# Main.net
KiCad netlist of a schematic drawn in Altium Designer
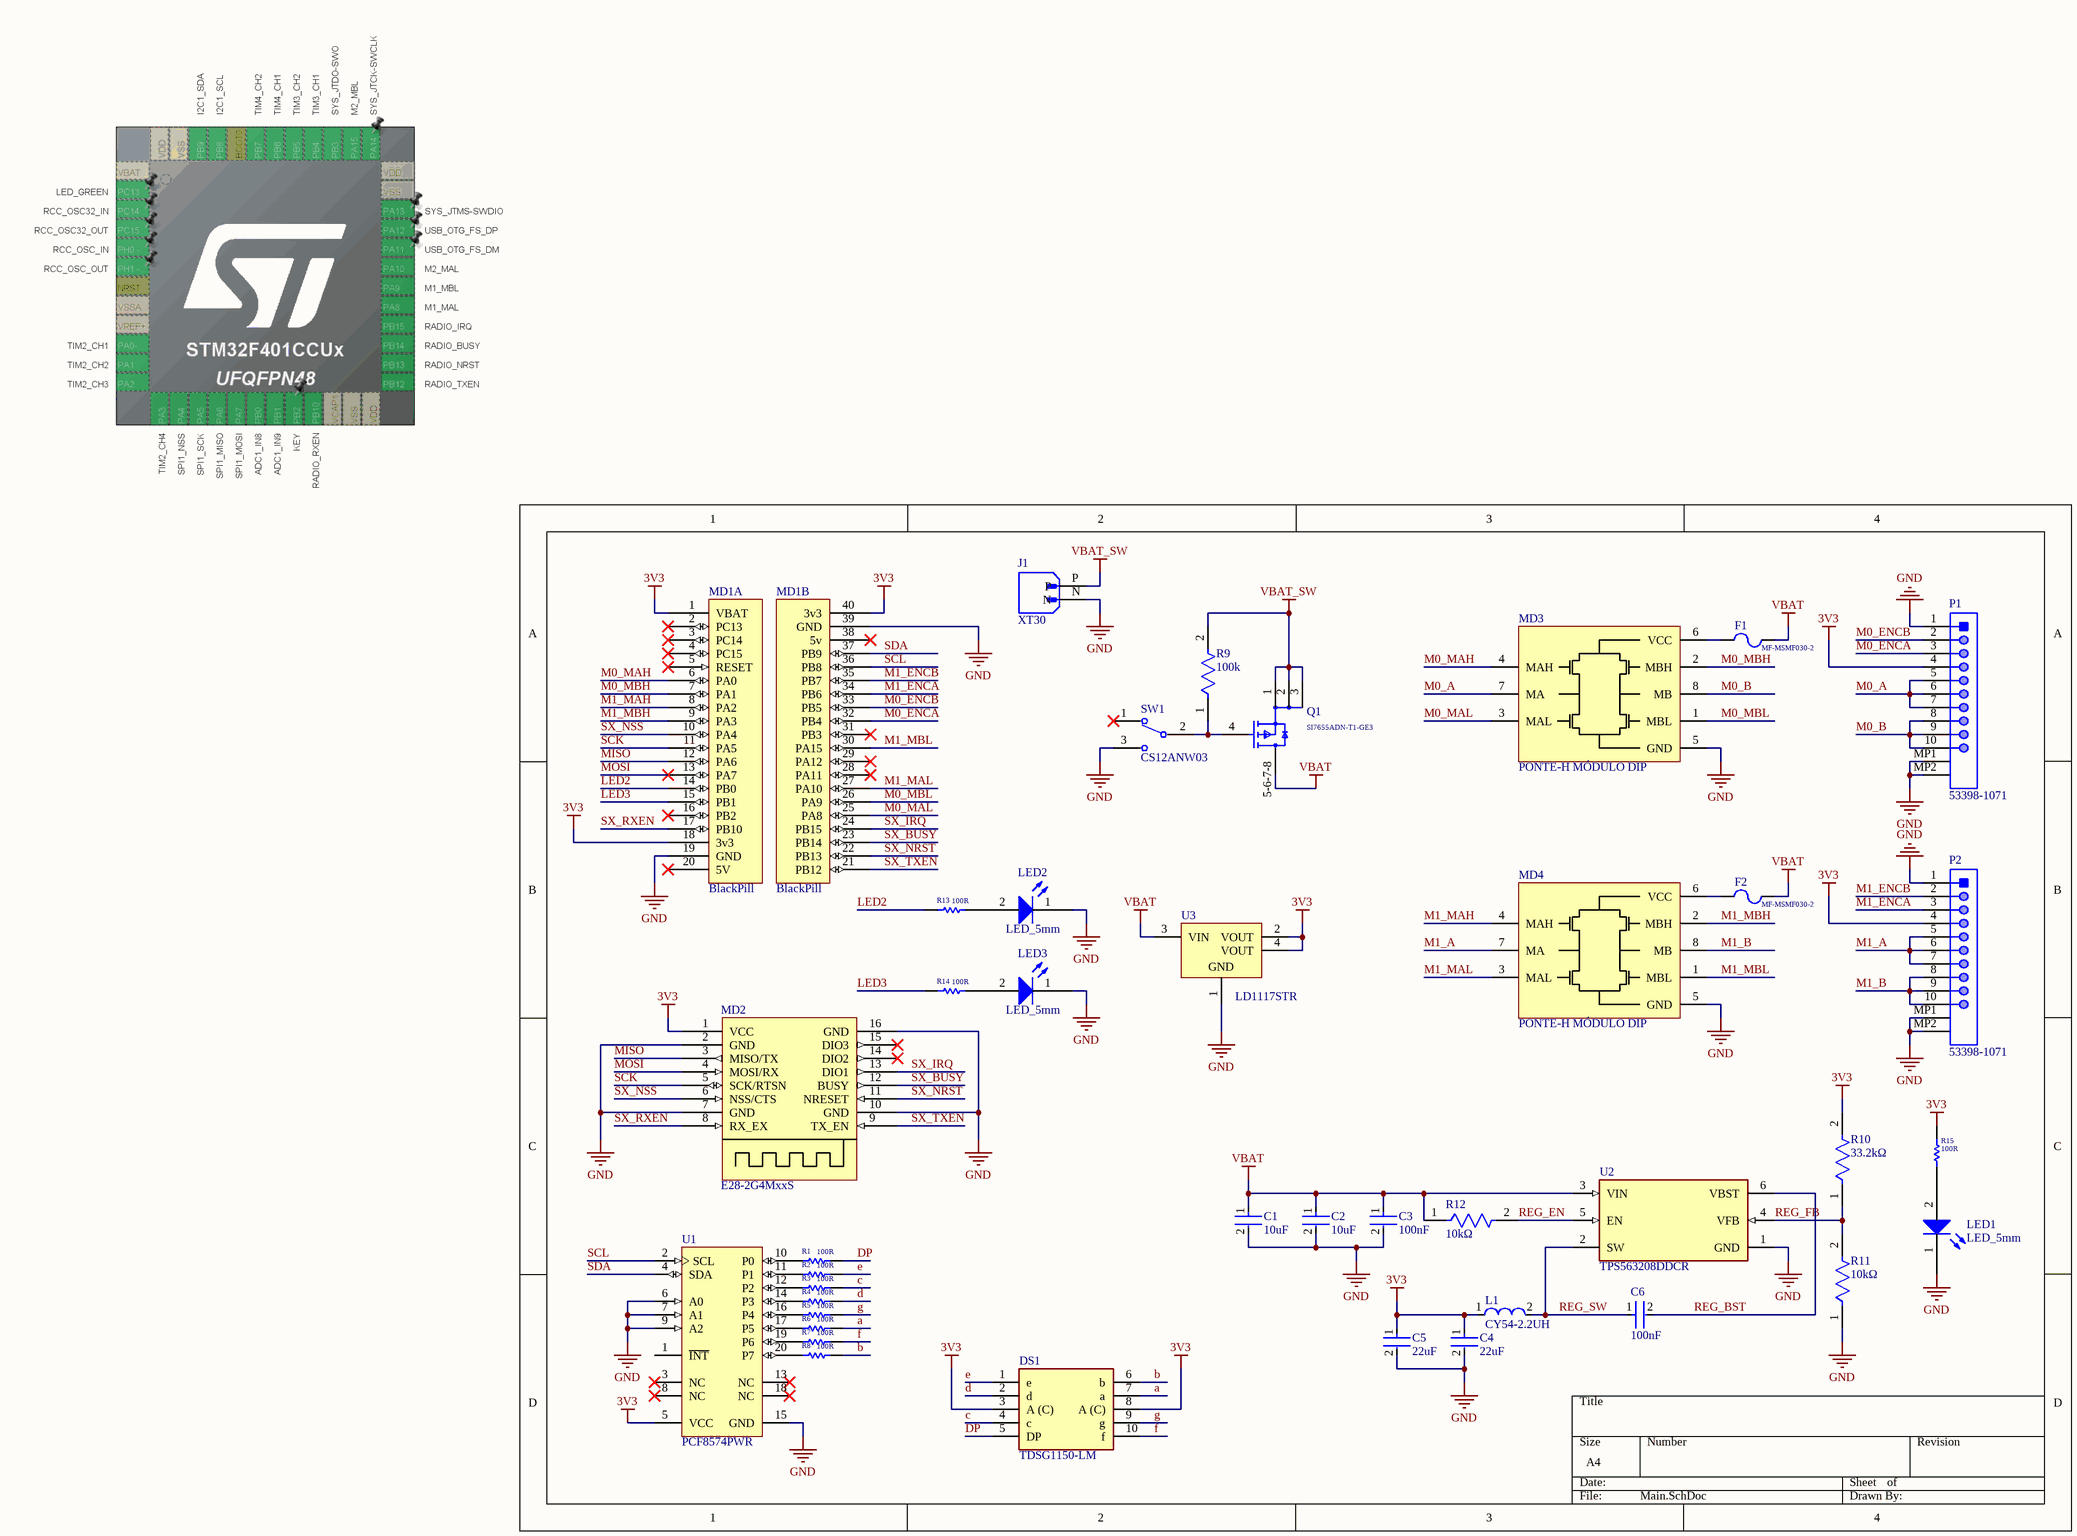
[diagram p0: Main.SchDoc]

(export (version "E")
  (design (tool "Eeschema 10.0.6"))
  (components
    (comp (ref "C1")
      (value "10uF")
      (footprint "FP-CL21-IPC_C")
      (description "CL21 Series 0805 10uF 16V ±10% Tolerance X5R Multilayer Ceramic Chip Capacitor")
      (fields (field (name "TOLERANCE") "10%") (field (name "VOLTAGE") "16V"))
      (libsource (lib "Altium Content Vault") (part "b4654b650e69147ec39a6b967a45e02"))
    )
    (comp (ref "C2")
      (value "10uF")
      (footprint "FP-CL21-IPC_C")
      (description "CL21 Series 0805 10uF 16V ±10% Tolerance X5R Multilayer Ceramic Chip Capacitor")
      (fields (field (name "TOLERANCE") "10%") (field (name "VOLTAGE") "16V"))
      (libsource (lib "Altium Content Vault") (part "b4654b650e69147ec39a6b967a45e02"))
    )
    (comp (ref "C3")
      (value "100nF")
      (footprint "FP-CL21-IPC_C")
      (description "CL21 Series 0805 100nF 25V ±10% Tolerance X7R Multilayer Ceramic Chip Capacitor")
      (fields (field (name "VOLTAGE") "25V") (field (name "TOLERANCE") "10%"))
      (libsource (lib "Altium Content Vault") (part "b4654b650e69147ec39a6b967a45e02"))
    )
    (comp (ref "C4")
      (value "22uF")
      (footprint "FP-CL21-IPC_C")
      (description "CL21 Series 0805 22uF 25V ±20% Tolerance X5R Multilayer Ceramic Chip Capacitor")
      (libsource (lib "Altium Content Vault") (part "b4654b650e69147ec39a6b967a45e02"))
    )
    (comp (ref "C5")
      (value "22uF")
      (footprint "FP-CL21-IPC_C")
      (description "CL21 Series 0805 22uF 25V ±20% Tolerance X5R Multilayer Ceramic Chip Capacitor")
      (libsource (lib "Altium Content Vault") (part "b4654b650e69147ec39a6b967a45e02"))
    )
    (comp (ref "C6")
      (value "100nF")
      (footprint "FP-CL21-IPC_C")
      (description "CL21 Series 0805 100nF 25V ±10% Tolerance X7R Multilayer Ceramic Chip Capacitor")
      (fields (field (name "VOLTAGE") "25V") (field (name "TOLERANCE") "10%"))
      (libsource (lib "Altium Content Vault") (part "b4654b650e69147ec39a6b967a45e02"))
    )
    (comp (ref "DS1")
      (value "TDSG1150-LM")
      (footprint "roboime:TDSG1150LM")
      (description "LED Displays & Accessories 7-Seg Green 7 mm Common anode")
      (fields (field (name "MOUSER PART NUMBER") "78-TDSG1150-LM"))
      (libsource (lib "roboime") (part "TDSG1150-LM"))
    )
    (comp (ref "F1")
      (value "MF-MSMF030-2")
      (footprint "BOUR-MF-MSMF030-2_V")
      (description "MF-MSMF Series - PTC Resettable Fuse, 30 V, -40 to 85 degC, 2-Pin SMD (1812), RoHS, Tape and Reel")
      (fields (field (name "MANUFACTURER") "Bourns") (field (name "PARTNUMBER") "MF-MSMF"))
      (libsource (lib "Altium Content Vault") (part "FUSE-2"))
    )
    (comp (ref "F2")
      (value "MF-MSMF030-2")
      (footprint "BOUR-MF-MSMF030-2_V")
      (description "MF-MSMF Series - PTC Resettable Fuse, 30 V, -40 to 85 degC, 2-Pin SMD (1812), RoHS, Tape and Reel")
      (fields (field (name "MANUFACTURER") "Bourns") (field (name "PARTNUMBER") "MF-MSMF"))
      (libsource (lib "Altium Content Vault") (part "FUSE-2"))
    )
    (comp (ref "J1")
      (value "XT30")
      (footprint "roboime:XT30")
      (description "Socket; DC supply; XT30; male; PIN: 2; on PCBs; THT; Colour: yellow")
      (fields (field (name "MF") "AMASS") (field (name "MP") "XT30PW-M"))
      (libsource (lib "roboime") (part "XT30"))
    )
    (comp (ref "L1")
      (value "CY54-2.2UH")
      (footprint "Gabriel:INDP5852X48N")
      (description "4A 2.2uH ±20% 22.1mΩ SMD,5.8x5.2mm Inductors (SMD) ROHS")
      (libsource (lib "Gabriel") (part "CY54-2.2UH"))
    )
    (comp (ref "LED1")
      (value "LED_5mm")
      (footprint "Gabriel:LED_5mm")
      (description "LED 5mm generic")
      (libsource (lib "Gabriel") (part "LED_5mm"))
    )
    (comp (ref "LED2")
      (value "LED_5mm")
      (footprint "Gabriel:LED_5mm")
      (description "LED 5mm generic")
      (libsource (lib "Gabriel") (part "LED_5mm"))
    )
    (comp (ref "LED3")
      (value "LED_5mm")
      (footprint "Gabriel:LED_5mm")
      (description "LED 5mm generic")
      (libsource (lib "Gabriel") (part "LED_5mm"))
    )
    (comp (ref "MD1")
      (value "BlackPill")
      (footprint "Gabriel:BlackPill")
      (description "STM32F4x1CxU6 BlackPill")
      (libsource (lib "Gabriel") (part "BlackPill"))
    )
    (comp (ref "MD2")
      (value "E28-2G4MxxS")
      (footprint "Gabriel:E28-2G4M12S")
      (description "E28-2G4MxxS Ebyte SX1280 Module")
      (libsource (lib "Gabriel") (part "E28-2G4MxxS"))
    )
    (comp (ref "MD3")
      (value "PONTE-H MÓDULO DIP")
      (footprint "roboime:PONTEH-PCB")
      (description "MÓDULO PONTE H DIP ROBOIME")
      (libsource (lib "roboime") (part "PONTEH-2016"))
    )
    (comp (ref "MD4")
      (value "PONTE-H MÓDULO DIP")
      (footprint "roboime:PONTEH-PCB")
      (description "MÓDULO PONTE H DIP ROBOIME")
      (libsource (lib "roboime") (part "PONTEH-2016"))
    )
    (comp (ref "P1")
      (value "53398-1071")
      (footprint "MOLX-53398-1071_V")
      (description "Male Header, Pitch 1.25 mm, 1 x 10 Position, Height 4.7 mm, -40 to 85 degC, RoHS, Tape and Reel")
      (fields (field (name "MANUFACTURER") "Molex"))
      (libsource (lib "Altium Content Vault") (part "CN-1P-2M-R10"))
    )
    (comp (ref "P2")
      (value "53398-1071")
      (footprint "MOLX-53398-1071_V")
      (description "Male Header, Pitch 1.25 mm, 1 x 10 Position, Height 4.7 mm, -40 to 85 degC, RoHS, Tape and Reel")
      (fields (field (name "MANUFACTURER") "Molex"))
      (libsource (lib "Altium Content Vault") (part "CN-1P-2M-R10"))
    )
    (comp (ref "Q1")
      (value "SI7655ADN-T1-GE3")
      (footprint "FP-C20-0862-SINGLE-MFG")
      (description "SI7655ADN-T1-GE3 20V 40A 3.6m次@10V20A 57W 1.1V@250米A P Channel PowerPAK 1212-8S MOSFETs ROHS")
      (libsource (lib "Altium Content Vault") (part "e312e2057707daa90b85c3ddf29a3cc"))
    )
    (comp (ref "R1")
      (value "100R")
      (footprint "RESC2013X50X30LL20T20")
      (fields (field (name "MANUFACTURER") "Vishay Dale") (field (name "PART NUMBER") "CRCW0805100RFKEA"))
      (libsource (lib "Altium Content Vault") (part "RES"))
    )
    (comp (ref "R2")
      (value "100R")
      (footprint "RESC2013X50X30LL20T20")
      (fields (field (name "MANUFACTURER") "Vishay Dale") (field (name "PART NUMBER") "CRCW0805100RFKEA"))
      (libsource (lib "Altium Content Vault") (part "RES"))
    )
    (comp (ref "R3")
      (value "100R")
      (footprint "RESC2013X50X30LL20T20")
      (fields (field (name "MANUFACTURER") "Vishay Dale") (field (name "PART NUMBER") "CRCW0805100RFKEA"))
      (libsource (lib "Altium Content Vault") (part "RES"))
    )
    (comp (ref "R4")
      (value "100R")
      (footprint "RESC2013X50X30LL20T20")
      (fields (field (name "MANUFACTURER") "Vishay Dale") (field (name "PART NUMBER") "CRCW0805100RFKEA"))
      (libsource (lib "Altium Content Vault") (part "RES"))
    )
    (comp (ref "R5")
      (value "100R")
      (footprint "RESC2013X50X30LL20T20")
      (fields (field (name "MANUFACTURER") "Vishay Dale") (field (name "PART NUMBER") "CRCW0805100RFKEA"))
      (libsource (lib "Altium Content Vault") (part "RES"))
    )
    (comp (ref "R6")
      (value "100R")
      (footprint "RESC2013X50X30LL20T20")
      (fields (field (name "MANUFACTURER") "Vishay Dale") (field (name "PART NUMBER") "CRCW0805100RFKEA"))
      (libsource (lib "Altium Content Vault") (part "RES"))
    )
    (comp (ref "R7")
      (value "100R")
      (footprint "RESC2013X50X30LL20T20")
      (fields (field (name "MANUFACTURER") "Vishay Dale") (field (name "PART NUMBER") "CRCW0805100RFKEA"))
      (libsource (lib "Altium Content Vault") (part "RES"))
    )
    (comp (ref "R8")
      (value "100R")
      (footprint "RESC2013X50X30LL20T20")
      (fields (field (name "MANUFACTURER") "Vishay Dale") (field (name "PART NUMBER") "CRCW0805100RFKEA"))
      (libsource (lib "Altium Content Vault") (part "RES"))
    )
    (comp (ref "R9")
      (value "100k")
      (footprint "FP-CRCW0805-e3-IPC_C")
      (description "RES Thick Film, 100kΩ, 1%, 0.125W, 100ppm/°C, 0805")
      (fields (field (name "TOLERANCE") "1%"))
      (libsource (lib "Altium Content Vault") (part "1029c3af85768c4190bb7ad29bc67b5"))
    )
    (comp (ref "R10")
      (value "33.2kΩ")
      (footprint "FP-CRCW0805-e3-IPC_C")
      (description "RES Thick Film, 33.2kΩ, 1%, 0.125W, 100ppm/°C, 0805")
      (fields (field (name "TOLERANCE") "1%"))
      (libsource (lib "Altium Content Vault") (part "1029c3af85768c4190bb7ad29bc67b5"))
    )
    (comp (ref "R11")
      (value "10kΩ")
      (footprint "FP-CRCW0805-e3-IPC_C")
      (description "RES Thick Film, 10kΩ, 1%, 0.125W, 100ppm/°C, 0805")
      (fields (field (name "TOLERANCE") "1%"))
      (libsource (lib "Altium Content Vault") (part "1029c3af85768c4190bb7ad29bc67b5"))
    )
    (comp (ref "R12")
      (value "10kΩ")
      (footprint "FP-CRCW0805-e3-IPC_C")
      (description "RES Thick Film, 10kΩ, 1%, 0.125W, 100ppm/°C, 0805")
      (fields (field (name "TOLERANCE") "1%"))
      (libsource (lib "Altium Content Vault") (part "1029c3af85768c4190bb7ad29bc67b5"))
    )
    (comp (ref "R13")
      (value "100R")
      (footprint "RESC2013X50X30LL20T20")
      (fields (field (name "MANUFACTURER") "Vishay Dale") (field (name "PART NUMBER") "CRCW0805100RFKEA"))
      (libsource (lib "Altium Content Vault") (part "RES"))
    )
    (comp (ref "R14")
      (value "100R")
      (footprint "RESC2013X50X30LL20T20")
      (fields (field (name "MANUFACTURER") "Vishay Dale") (field (name "PART NUMBER") "CRCW0805100RFKEA"))
      (libsource (lib "Altium Content Vault") (part "RES"))
    )
    (comp (ref "R15")
      (value "100R")
      (footprint "RESC2013X50X30LL20T20")
      (fields (field (name "MANUFACTURER") "Vishay Dale") (field (name "PART NUMBER") "CRCW0805100RFKEA"))
      (libsource (lib "Altium Content Vault") (part "RES"))
    )
    (comp (ref "SW1")
      (value "CS12ANW03")
      (footprint "FP-CS12ANW03-MFG")
      (description "SWITCH SLIDE SPDT 3A 125V")
      (libsource (lib "Altium Content Vault") (part "12161840acc88c497b895bf2e19a5b1"))
    )
    (comp (ref "U1")
      (value "PCF8574PWR")
      (footprint "PW0020A_L")
      (fields (field (name "MANUFACTURER") "Texas Instruments"))
      (libsource (lib "Altium Content Vault") (part "TI-PCF8574-TSSOP_PW-20"))
    )
    (comp (ref "U2")
      (value "TPS563208DDCR")
      (footprint "FP-DDC0006A-MFG")
      (description "IC REG BUCK ADJ 3A TSOT23-6")
      (libsource (lib "Altium Content Vault") (part "aba72cbc9cf0ad42a1bc8855c06655c"))
    )
    (comp (ref "U3")
      (value "LD1117STR")
      (footprint "SOT-223_L")
      (description "Adjustable Low Drop Voltage Regulator, 1.25 to 15V, 4-Pin SOT-223, Tape and Reel")
      (libsource (lib "Altium Content Vault") (part "PM-REG-LD1117-SOT4"))
    )
  )
  (nets
    (net (code "1") (name "/DP") (class "Default")
      (node (ref "DS1") (pin "5") (pinfunction "DP_5") (pintype "passive"))
      (node (ref "R1") (pin "2") (pinfunction "2_2") (pintype "passive"))
    )
    (net (code "2") (name "/LED2") (class "Default")
      (node (ref "MD1") (pin "14") (pinfunction "PB0_14") (pintype "bidirectional"))
      (node (ref "R13") (pin "1") (pinfunction "1_1") (pintype "passive"))
    )
    (net (code "3") (name "/LED3") (class "Default")
      (node (ref "MD1") (pin "15") (pinfunction "PB1_15") (pintype "bidirectional"))
      (node (ref "R14") (pin "1") (pinfunction "1_1") (pintype "passive"))
    )
    (net (code "4") (name "/M0_A") (class "Default")
      (node (ref "MD3") (pin "7") (pinfunction "MA_7") (pintype "passive"))
      (node (ref "P1") (pin "5") (pinfunction "5_5") (pintype "passive"))
      (node (ref "P1") (pin "6") (pinfunction "6_6") (pintype "passive"))
      (node (ref "P1") (pin "7") (pinfunction "7_7") (pintype "passive"))
    )
    (net (code "5") (name "/M0_B") (class "Default")
      (node (ref "MD3") (pin "8") (pinfunction "MB_8") (pintype "passive"))
      (node (ref "P1") (pin "10") (pinfunction "10_10") (pintype "passive"))
      (node (ref "P1") (pin "8") (pinfunction "8_8") (pintype "passive"))
      (node (ref "P1") (pin "9") (pinfunction "9_9") (pintype "passive"))
    )
    (net (code "6") (name "/M0_ENCA") (class "Default")
      (node (ref "MD1") (pin "32") (pinfunction "PB4_32") (pintype "bidirectional"))
      (node (ref "P1") (pin "3") (pinfunction "3_3") (pintype "passive"))
    )
    (net (code "7") (name "/M0_ENCB") (class "Default")
      (node (ref "MD1") (pin "33") (pinfunction "PB5_33") (pintype "bidirectional"))
      (node (ref "P1") (pin "2") (pinfunction "2_2") (pintype "passive"))
    )
    (net (code "8") (name "/M0_MAH") (class "Default")
      (node (ref "MD1") (pin "6") (pinfunction "PA0_6") (pintype "bidirectional"))
      (node (ref "MD3") (pin "4") (pinfunction "MAH_4") (pintype "passive"))
    )
    (net (code "9") (name "/M0_MAL") (class "Default")
      (node (ref "MD1") (pin "25") (pinfunction "PA8_25") (pintype "bidirectional"))
      (node (ref "MD3") (pin "3") (pinfunction "MAL_3") (pintype "passive"))
    )
    (net (code "10") (name "/M0_MBH") (class "Default")
      (node (ref "MD1") (pin "7") (pinfunction "PA1_7") (pintype "bidirectional"))
      (node (ref "MD3") (pin "2") (pinfunction "MBH_2") (pintype "passive"))
    )
    (net (code "11") (name "/M0_MBL") (class "Default")
      (node (ref "MD1") (pin "26") (pinfunction "PA9_26") (pintype "bidirectional"))
      (node (ref "MD3") (pin "1") (pinfunction "MBL_1") (pintype "passive"))
    )
    (net (code "12") (name "/M1_A") (class "Default")
      (node (ref "MD4") (pin "7") (pinfunction "MA_7") (pintype "passive"))
      (node (ref "P2") (pin "5") (pinfunction "5_5") (pintype "passive"))
      (node (ref "P2") (pin "6") (pinfunction "6_6") (pintype "passive"))
      (node (ref "P2") (pin "7") (pinfunction "7_7") (pintype "passive"))
    )
    (net (code "13") (name "/M1_B") (class "Default")
      (node (ref "MD4") (pin "8") (pinfunction "MB_8") (pintype "passive"))
      (node (ref "P2") (pin "10") (pinfunction "10_10") (pintype "passive"))
      (node (ref "P2") (pin "8") (pinfunction "8_8") (pintype "passive"))
      (node (ref "P2") (pin "9") (pinfunction "9_9") (pintype "passive"))
    )
    (net (code "14") (name "/M1_ENCA") (class "Default")
      (node (ref "MD1") (pin "34") (pinfunction "PB6_34") (pintype "bidirectional"))
      (node (ref "P2") (pin "3") (pinfunction "3_3") (pintype "passive"))
    )
    (net (code "15") (name "/M1_ENCB") (class "Default")
      (node (ref "MD1") (pin "35") (pinfunction "PB7_35") (pintype "bidirectional"))
      (node (ref "P2") (pin "2") (pinfunction "2_2") (pintype "passive"))
    )
    (net (code "16") (name "/M1_MAH") (class "Default")
      (node (ref "MD1") (pin "8") (pinfunction "PA2_8") (pintype "bidirectional"))
      (node (ref "MD4") (pin "4") (pinfunction "MAH_4") (pintype "passive"))
    )
    (net (code "17") (name "/M1_MAL") (class "Default")
      (node (ref "MD1") (pin "27") (pinfunction "PA10_27") (pintype "bidirectional"))
      (node (ref "MD4") (pin "3") (pinfunction "MAL_3") (pintype "passive"))
    )
    (net (code "18") (name "/M1_MBH") (class "Default")
      (node (ref "MD1") (pin "9") (pinfunction "PA3_9") (pintype "bidirectional"))
      (node (ref "MD4") (pin "2") (pinfunction "MBH_2") (pintype "passive"))
    )
    (net (code "19") (name "/M1_MBL") (class "Default")
      (node (ref "MD1") (pin "30") (pinfunction "PA15_30") (pintype "bidirectional"))
      (node (ref "MD4") (pin "1") (pinfunction "MBL_1") (pintype "passive"))
    )
    (net (code "20") (name "/MISO") (class "Default")
      (node (ref "MD1") (pin "12") (pinfunction "PA6_12") (pintype "bidirectional"))
      (node (ref "MD2") (pin "3") (pinfunction "MISO/TX_3") (pintype "output"))
    )
    (net (code "21") (name "/MOSI") (class "Default")
      (node (ref "MD1") (pin "13") (pinfunction "PA7_13") (pintype "bidirectional"))
      (node (ref "MD2") (pin "4") (pinfunction "MOSI/RX_4") (pintype "input"))
    )
    (net (code "22") (name "/REG_BST") (class "Default")
      (node (ref "C6") (pin "2") (pinfunction "2_2") (pintype "passive"))
      (node (ref "U2") (pin "6") (pinfunction "VBST_6") (pintype "power_in"))
    )
    (net (code "23") (name "/REG_EN") (class "Default")
      (node (ref "R12") (pin "2") (pinfunction "2_2") (pintype "passive"))
      (node (ref "U2") (pin "5") (pinfunction "EN_5") (pintype "input"))
    )
    (net (code "24") (name "/REG_FB") (class "Default")
      (node (ref "R10") (pin "1") (pinfunction "1_1") (pintype "passive"))
      (node (ref "R11") (pin "2") (pinfunction "2_2") (pintype "passive"))
      (node (ref "U2") (pin "4") (pinfunction "VFB_4") (pintype "input"))
    )
    (net (code "25") (name "/REG_SW") (class "Default")
      (node (ref "C6") (pin "1") (pinfunction "1_1") (pintype "passive"))
      (node (ref "L1") (pin "2") (pintype "passive"))
      (node (ref "U2") (pin "2") (pinfunction "SW_2") (pintype "power_in"))
    )
    (net (code "26") (name "/SCK") (class "Default")
      (node (ref "MD1") (pin "11") (pinfunction "PA5_11") (pintype "bidirectional"))
      (node (ref "MD2") (pin "5") (pinfunction "SCK/RTSN_5") (pintype "bidirectional"))
    )
    (net (code "27") (name "/SCL") (class "Default")
      (node (ref "MD1") (pin "36") (pinfunction "PB8_36") (pintype "bidirectional"))
      (node (ref "U1") (pin "2") (pinfunction "SCL_2") (pintype "input"))
    )
    (net (code "28") (name "/SDA") (class "Default")
      (node (ref "MD1") (pin "37") (pinfunction "PB9_37") (pintype "bidirectional"))
      (node (ref "U1") (pin "4") (pinfunction "SDA_4") (pintype "bidirectional"))
    )
    (net (code "29") (name "/SX_BUSY") (class "Default")
      (node (ref "MD1") (pin "23") (pinfunction "PB14_23") (pintype "bidirectional"))
      (node (ref "MD2") (pin "12") (pinfunction "BUSY_12") (pintype "output"))
    )
    (net (code "30") (name "/SX_IRQ") (class "Default")
      (node (ref "MD1") (pin "24") (pinfunction "PB15_24") (pintype "bidirectional"))
      (node (ref "MD2") (pin "13") (pinfunction "DIO1_13") (pintype "output"))
    )
    (net (code "31") (name "/SX_NRST") (class "Default")
      (node (ref "MD1") (pin "22") (pinfunction "PB13_22") (pintype "bidirectional"))
      (node (ref "MD2") (pin "11") (pinfunction "NRESET_11") (pintype "input"))
    )
    (net (code "32") (name "/SX_NSS") (class "Default")
      (node (ref "MD1") (pin "10") (pinfunction "PA4_10") (pintype "bidirectional"))
      (node (ref "MD2") (pin "6") (pinfunction "NSS/CTS_6") (pintype "input"))
    )
    (net (code "33") (name "/SX_RXEN") (class "Default")
      (node (ref "MD1") (pin "17") (pinfunction "PB10_17") (pintype "bidirectional"))
      (node (ref "MD2") (pin "8") (pinfunction "RX_EX_8") (pintype "input"))
    )
    (net (code "34") (name "/SX_TXEN") (class "Default")
      (node (ref "MD1") (pin "21") (pinfunction "PB12_21") (pintype "bidirectional"))
      (node (ref "MD2") (pin "9") (pinfunction "TX_EN_9") (pintype "input"))
    )
    (net (code "35") (name "/a") (class "Default")
      (node (ref "DS1") (pin "7") (pinfunction "a_7") (pintype "passive"))
      (node (ref "R6") (pin "2") (pinfunction "2_2") (pintype "passive"))
    )
    (net (code "36") (name "/b") (class "Default")
      (node (ref "DS1") (pin "6") (pinfunction "b_6") (pintype "passive"))
      (node (ref "R8") (pin "2") (pinfunction "2_2") (pintype "passive"))
    )
    (net (code "37") (name "/c") (class "Default")
      (node (ref "DS1") (pin "4") (pinfunction "c_4") (pintype "passive"))
      (node (ref "R3") (pin "2") (pinfunction "2_2") (pintype "passive"))
    )
    (net (code "38") (name "/d") (class "Default")
      (node (ref "DS1") (pin "2") (pinfunction "d_2") (pintype "passive"))
      (node (ref "R4") (pin "2") (pinfunction "2_2") (pintype "passive"))
    )
    (net (code "39") (name "/e") (class "Default")
      (node (ref "DS1") (pin "1") (pinfunction "e_1") (pintype "passive"))
      (node (ref "R2") (pin "2") (pinfunction "2_2") (pintype "passive"))
    )
    (net (code "40") (name "/f") (class "Default")
      (node (ref "DS1") (pin "10") (pinfunction "f_10") (pintype "passive"))
      (node (ref "R7") (pin "2") (pinfunction "2_2") (pintype "passive"))
    )
    (net (code "41") (name "/g") (class "Default")
      (node (ref "DS1") (pin "9") (pinfunction "g_9") (pintype "passive"))
      (node (ref "R5") (pin "2") (pinfunction "2_2") (pintype "passive"))
    )
    (net (code "42") (name "3V3") (class "Default")
      (node (ref "C4") (pin "1") (pinfunction "1_1") (pintype "passive"))
      (node (ref "C5") (pin "1") (pinfunction "1_1") (pintype "passive"))
      (node (ref "DS1") (pin "3") (pinfunction "A_(C)_3") (pintype "passive"))
      (node (ref "DS1") (pin "8") (pinfunction "A_(C)_8") (pintype "passive"))
      (node (ref "L1") (pin "1") (pintype "passive"))
      (node (ref "MD1") (pin "1") (pinfunction "VBAT_1") (pintype "power_in"))
      (node (ref "MD1") (pin "18") (pinfunction "3v3_18") (pintype "power_in"))
      (node (ref "MD1") (pin "40") (pinfunction "3v3_40") (pintype "power_in"))
      (node (ref "MD2") (pin "1") (pinfunction "VCC_1") (pintype "power_in"))
      (node (ref "P1") (pin "4") (pinfunction "4_4") (pintype "passive"))
      (node (ref "P2") (pin "4") (pinfunction "4_4") (pintype "passive"))
      (node (ref "R10") (pin "2") (pinfunction "2_2") (pintype "passive"))
      (node (ref "R15") (pin "2") (pinfunction "2_2") (pintype "passive"))
      (node (ref "U1") (pin "5") (pinfunction "VCC_5") (pintype "power_in"))
      (node (ref "U3") (pin "2") (pinfunction "VOUT_2") (pintype "power_in"))
      (node (ref "U3") (pin "4") (pinfunction "VOUT_4") (pintype "power_in"))
    )
    (net (code "43") (name "GND") (class "Default")
      (node (ref "C1") (pin "2") (pinfunction "2_2") (pintype "passive"))
      (node (ref "C2") (pin "2") (pinfunction "2_2") (pintype "passive"))
      (node (ref "C3") (pin "2") (pinfunction "2_2") (pintype "passive"))
      (node (ref "C4") (pin "2") (pinfunction "2_2") (pintype "passive"))
      (node (ref "C5") (pin "2") (pinfunction "2_2") (pintype "passive"))
      (node (ref "J1") (pin "N") (pinfunction "N_N") (pintype "power_in"))
      (node (ref "LED1") (pin "1") (pinfunction "K_1") (pintype "passive"))
      (node (ref "LED2") (pin "1") (pinfunction "K_1") (pintype "passive"))
      (node (ref "LED3") (pin "1") (pinfunction "K_1") (pintype "passive"))
      (node (ref "MD1") (pin "19") (pinfunction "GND_19") (pintype "power_in"))
      (node (ref "MD1") (pin "39") (pinfunction "GND_39") (pintype "power_in"))
      (node (ref "MD2") (pin "10") (pinfunction "GND_10") (pintype "power_in"))
      (node (ref "MD2") (pin "16") (pinfunction "GND_16") (pintype "power_in"))
      (node (ref "MD2") (pin "2") (pinfunction "GND_2") (pintype "power_in"))
      (node (ref "MD2") (pin "7") (pinfunction "GND_7") (pintype "power_in"))
      (node (ref "MD3") (pin "5") (pinfunction "GND_5") (pintype "passive"))
      (node (ref "MD4") (pin "5") (pinfunction "GND_5") (pintype "passive"))
      (node (ref "P1") (pin "1") (pinfunction "1_1") (pintype "passive"))
      (node (ref "P1") (pin "MP1") (pinfunction "MP1_MP1") (pintype "passive"))
      (node (ref "P1") (pin "MP2") (pinfunction "MP2_MP2") (pintype "passive"))
      (node (ref "P2") (pin "1") (pinfunction "1_1") (pintype "passive"))
      (node (ref "P2") (pin "MP1") (pinfunction "MP1_MP1") (pintype "passive"))
      (node (ref "P2") (pin "MP2") (pinfunction "MP2_MP2") (pintype "passive"))
      (node (ref "R11") (pin "1") (pinfunction "1_1") (pintype "passive"))
      (node (ref "SW1") (pin "3") (pinfunction "3_3") (pintype "passive"))
      (node (ref "U1") (pin "15") (pinfunction "GND_15") (pintype "power_in"))
      (node (ref "U1") (pin "6") (pinfunction "A0_6") (pintype "input"))
      (node (ref "U1") (pin "7") (pinfunction "A1_7") (pintype "input"))
      (node (ref "U1") (pin "9") (pinfunction "A2_9") (pintype "input"))
      (node (ref "U2") (pin "1") (pinfunction "GND_1") (pintype "power_in"))
      (node (ref "U3") (pin "1") (pinfunction "GND_1") (pintype "power_in"))
    )
    (net (code "44") (name "Net-(LED1-A)") (class "Default")
      (node (ref "LED1") (pin "2") (pinfunction "A_2") (pintype "passive"))
      (node (ref "R15") (pin "1") (pinfunction "1_1") (pintype "passive"))
    )
    (net (code "45") (name "Net-(LED2-A)") (class "Default")
      (node (ref "LED2") (pin "2") (pinfunction "A_2") (pintype "passive"))
      (node (ref "R13") (pin "2") (pinfunction "2_2") (pintype "passive"))
    )
    (net (code "46") (name "Net-(LED3-A)") (class "Default")
      (node (ref "LED3") (pin "2") (pinfunction "A_2") (pintype "passive"))
      (node (ref "R14") (pin "2") (pinfunction "2_2") (pintype "passive"))
    )
    (net (code "47") (name "Net-(MD3-VCC)") (class "Default")
      (node (ref "F1") (pin "1") (pinfunction "1_1") (pintype "passive"))
      (node (ref "MD3") (pin "6") (pinfunction "VCC_6") (pintype "passive"))
    )
    (net (code "48") (name "Net-(MD4-VCC)") (class "Default")
      (node (ref "F2") (pin "1") (pinfunction "1_1") (pintype "passive"))
      (node (ref "MD4") (pin "6") (pinfunction "VCC_6") (pintype "passive"))
    )
    (net (code "49") (name "Net-(Q1-G)") (class "Default")
      (node (ref "Q1") (pin "4") (pinfunction "G_4") (pintype "passive"))
      (node (ref "R9") (pin "1") (pinfunction "1_1") (pintype "passive"))
      (node (ref "SW1") (pin "2") (pinfunction "2(COM)_2") (pintype "passive"))
    )
    (net (code "50") (name "Net-(U1-P0)") (class "Default")
      (node (ref "R1") (pin "1") (pinfunction "1_1") (pintype "passive"))
      (node (ref "U1") (pin "10") (pinfunction "P0_10") (pintype "bidirectional"))
    )
    (net (code "51") (name "Net-(U1-P1)") (class "Default")
      (node (ref "R2") (pin "1") (pinfunction "1_1") (pintype "passive"))
      (node (ref "U1") (pin "11") (pinfunction "P1_11") (pintype "bidirectional"))
    )
    (net (code "52") (name "Net-(U1-P2)") (class "Default")
      (node (ref "R3") (pin "1") (pinfunction "1_1") (pintype "passive"))
      (node (ref "U1") (pin "12") (pinfunction "P2_12") (pintype "bidirectional"))
    )
    (net (code "53") (name "Net-(U1-P3)") (class "Default")
      (node (ref "R4") (pin "1") (pinfunction "1_1") (pintype "passive"))
      (node (ref "U1") (pin "14") (pinfunction "P3_14") (pintype "bidirectional"))
    )
    (net (code "54") (name "Net-(U1-P4)") (class "Default")
      (node (ref "R5") (pin "1") (pinfunction "1_1") (pintype "passive"))
      (node (ref "U1") (pin "16") (pinfunction "P4_16") (pintype "bidirectional"))
    )
    (net (code "55") (name "Net-(U1-P5)") (class "Default")
      (node (ref "R6") (pin "1") (pinfunction "1_1") (pintype "passive"))
      (node (ref "U1") (pin "17") (pinfunction "P5_17") (pintype "bidirectional"))
    )
    (net (code "56") (name "Net-(U1-P6)") (class "Default")
      (node (ref "R7") (pin "1") (pinfunction "1_1") (pintype "passive"))
      (node (ref "U1") (pin "19") (pinfunction "P6_19") (pintype "bidirectional"))
    )
    (net (code "57") (name "Net-(U1-P7)") (class "Default")
      (node (ref "R8") (pin "1") (pinfunction "1_1") (pintype "passive"))
      (node (ref "U1") (pin "20") (pinfunction "P7_20") (pintype "bidirectional"))
    )
    (net (code "58") (name "VBAT") (class "Default")
      (node (ref "C1") (pin "1") (pinfunction "1_1") (pintype "passive"))
      (node (ref "C2") (pin "1") (pinfunction "1_1") (pintype "passive"))
      (node (ref "C3") (pin "1") (pinfunction "1_1") (pintype "passive"))
      (node (ref "F1") (pin "2") (pinfunction "2_2") (pintype "passive"))
      (node (ref "F2") (pin "2") (pinfunction "2_2") (pintype "passive"))
      (node (ref "Q1") (pin "5-6-7-8") (pinfunction "D_5-6-7-8") (pintype "passive"))
      (node (ref "R12") (pin "1") (pinfunction "1_1") (pintype "passive"))
      (node (ref "U2") (pin "3") (pinfunction "VIN_3") (pintype "input"))
      (node (ref "U3") (pin "3") (pinfunction "VIN_3") (pintype "power_in"))
    )
    (net (code "59") (name "VBAT_SW") (class "Default")
      (node (ref "J1") (pin "P") (pinfunction "P_P") (pintype "power_in"))
      (node (ref "Q1") (pin "1") (pinfunction "S_1") (pintype "passive"))
      (node (ref "Q1") (pin "2") (pinfunction "S_2") (pintype "passive"))
      (node (ref "Q1") (pin "3") (pinfunction "S_3") (pintype "passive"))
      (node (ref "R9") (pin "2") (pinfunction "2_2") (pintype "passive"))
    )
    (net (code "60") (name "unconnected-(MD1A-5V-Pad20)") (class "Default")
      (node (ref "MD1") (pin "20") (pinfunction "5V_20") (pintype "power_in+no_connect"))
    )
    (net (code "61") (name "unconnected-(MD1A-PB2-Pad16)") (class "Default")
      (node (ref "MD1") (pin "16") (pinfunction "PB2_16") (pintype "bidirectional+no_connect"))
    )
    (net (code "62") (name "unconnected-(MD1A-PC13-Pad2)") (class "Default")
      (node (ref "MD1") (pin "2") (pinfunction "PC13_2") (pintype "bidirectional+no_connect"))
    )
    (net (code "63") (name "unconnected-(MD1A-PC14-Pad3)") (class "Default")
      (node (ref "MD1") (pin "3") (pinfunction "PC14_3") (pintype "bidirectional+no_connect"))
    )
    (net (code "64") (name "unconnected-(MD1A-PC15-Pad4)") (class "Default")
      (node (ref "MD1") (pin "4") (pinfunction "PC15_4") (pintype "bidirectional+no_connect"))
    )
    (net (code "65") (name "unconnected-(MD1A-RESET-Pad5)") (class "Default")
      (node (ref "MD1") (pin "5") (pinfunction "RESET_5") (pintype "input+no_connect"))
    )
    (net (code "66") (name "unconnected-(MD1B-5v-Pad38)") (class "Default")
      (node (ref "MD1") (pin "38") (pinfunction "5v_38") (pintype "power_in+no_connect"))
    )
    (net (code "67") (name "unconnected-(MD1B-PA11-Pad28)") (class "Default")
      (node (ref "MD1") (pin "28") (pinfunction "PA11_28") (pintype "bidirectional+no_connect"))
    )
    (net (code "68") (name "unconnected-(MD1B-PA12-Pad29)") (class "Default")
      (node (ref "MD1") (pin "29") (pinfunction "PA12_29") (pintype "bidirectional+no_connect"))
    )
    (net (code "69") (name "unconnected-(MD1B-PB3-Pad31)") (class "Default")
      (node (ref "MD1") (pin "31") (pinfunction "PB3_31") (pintype "bidirectional+no_connect"))
    )
    (net (code "70") (name "unconnected-(MD2-DIO2-Pad14)") (class "Default")
      (node (ref "MD2") (pin "14") (pinfunction "DIO2_14") (pintype "output+no_connect"))
    )
    (net (code "71") (name "unconnected-(MD2-DIO3-Pad15)") (class "Default")
      (node (ref "MD2") (pin "15") (pinfunction "DIO3_15") (pintype "output+no_connect"))
    )
    (net (code "72") (name "unconnected-(SW1-Pad1)") (class "Default")
      (node (ref "SW1") (pin "1") (pinfunction "1_1") (pintype "passive+no_connect"))
    )
    (net (code "73") (name "unconnected-(U1-NC-Pad3)") (class "Default")
      (node (ref "U1") (pin "3") (pinfunction "NC_3") (pintype "passive+no_connect"))
    )
    (net (code "74") (name "unconnected-(U1-NC-Pad8)") (class "Default")
      (node (ref "U1") (pin "8") (pinfunction "NC_8") (pintype "passive+no_connect"))
    )
    (net (code "75") (name "unconnected-(U1-NC-Pad13)") (class "Default")
      (node (ref "U1") (pin "13") (pinfunction "NC_13") (pintype "passive+no_connect"))
    )
    (net (code "76") (name "unconnected-(U1-NC-Pad18)") (class "Default")
      (node (ref "U1") (pin "18") (pinfunction "NC_18") (pintype "passive+no_connect"))
    )
    (net (code "77") (name "unconnected-(U1-~{INT}-Pad1)") (class "Default")
      (node (ref "U1") (pin "1") (pinfunction "~{INT}_1") (pintype "open_collector"))
    )
  )
)
